# res.net
KiCad netlist of a schematic drawn in EAGLE
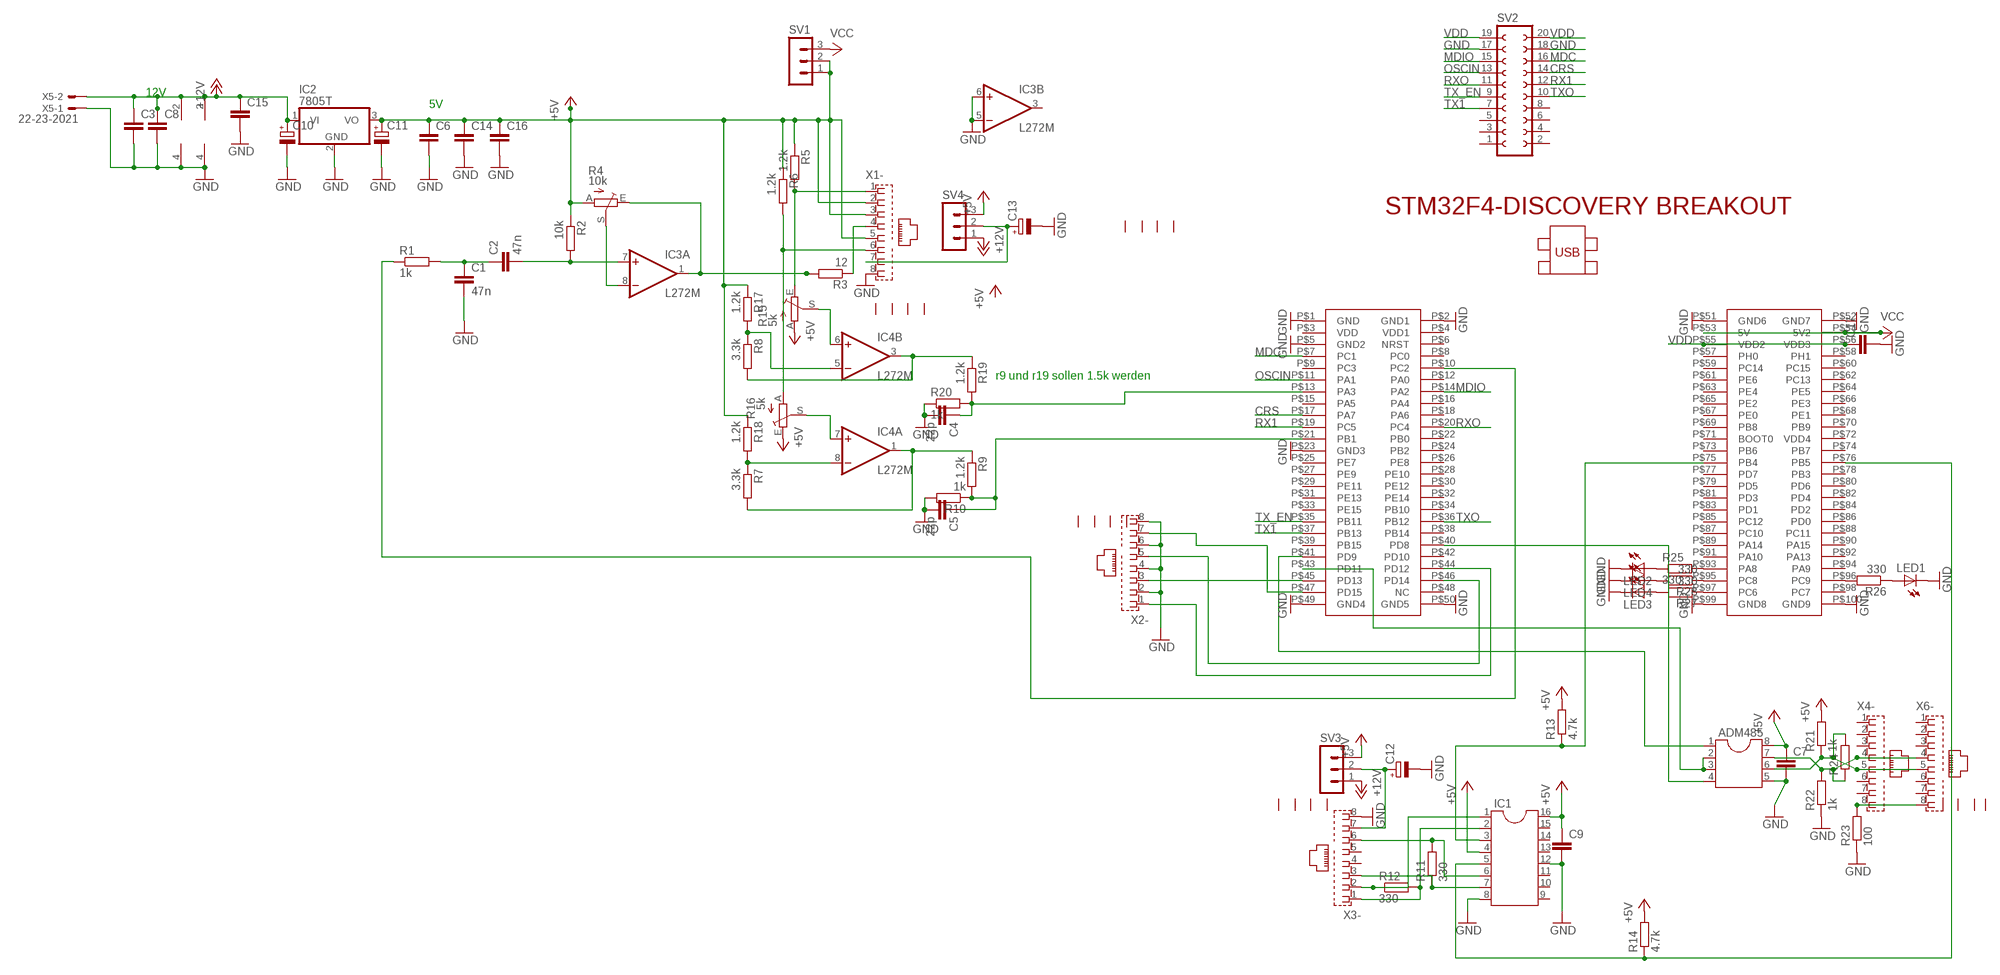
[diagram p0: schematic, sheet 1]

(export (version "E")
  (design (tool "Eeschema 10.0.6"))
  (components
    (comp (ref "ADM485")
      (value "DIL8")
      (footprint "eagle-import:DIL08")
      (libsource (lib "eagle-import") (part "DIL8"))
    )
    (comp (ref "C1")
      (value "47n")
      (footprint "eagle-import:C050-025X075")
      (libsource (lib "eagle-import") (part "C-EU050-025X075"))
    )
    (comp (ref "C2")
      (value "47n")
      (footprint "eagle-import:C050-025X075")
      (libsource (lib "eagle-import") (part "C-EU050-025X075"))
    )
    (comp (ref "C3")
      (value "C-EU050-025X075")
      (footprint "eagle-import:C050-025X075")
      (libsource (lib "eagle-import") (part "C-EU050-025X075"))
    )
    (comp (ref "C4")
      (value "22p")
      (footprint "eagle-import:C050-025X075")
      (libsource (lib "eagle-import") (part "C-EU050-025X075"))
    )
    (comp (ref "C5")
      (value "22p")
      (footprint "eagle-import:C050-025X075")
      (libsource (lib "eagle-import") (part "C-EU050-025X075"))
    )
    (comp (ref "C6")
      (value "C-EU050-025X075")
      (footprint "eagle-import:C050-025X075")
      (libsource (lib "eagle-import") (part "C-EU050-025X075"))
    )
    (comp (ref "C7")
      (value "C-EU050-025X075")
      (footprint "eagle-import:C050-025X075")
      (libsource (lib "eagle-import") (part "C-EU050-025X075"))
    )
    (comp (ref "C8")
      (value "C-EU050-025X075")
      (footprint "eagle-import:C050-025X075")
      (libsource (lib "eagle-import") (part "C-EU050-025X075"))
    )
    (comp (ref "C9")
      (value "C-EU050-025X075")
      (footprint "eagle-import:C050-025X075")
      (libsource (lib "eagle-import") (part "C-EU050-025X075"))
    )
    (comp (ref "C10")
      (value "CPOL-EUE2.5-5")
      (footprint "eagle-import:E2,5-5")
      (libsource (lib "eagle-import") (part "CPOL-EUE2.5-5"))
    )
    (comp (ref "C11")
      (value "CPOL-EUE2.5-5")
      (footprint "eagle-import:E2,5-5")
      (libsource (lib "eagle-import") (part "CPOL-EUE2.5-5"))
    )
    (comp (ref "C12")
      (value "CPOL-EUE2.5-5")
      (footprint "eagle-import:E2,5-5")
      (libsource (lib "eagle-import") (part "CPOL-EUE2.5-5"))
    )
    (comp (ref "C13")
      (value "CPOL-EUE2.5-5")
      (footprint "eagle-import:E2,5-5")
      (libsource (lib "eagle-import") (part "CPOL-EUE2.5-5"))
    )
    (comp (ref "C14")
      (value "C-EU050-025X075")
      (footprint "eagle-import:C050-025X075")
      (libsource (lib "eagle-import") (part "C-EU050-025X075"))
    )
    (comp (ref "C15")
      (value "C-EU050-025X075")
      (footprint "eagle-import:C050-025X075")
      (libsource (lib "eagle-import") (part "C-EU050-025X075"))
    )
    (comp (ref "C16")
      (value "C-EU050-025X075")
      (footprint "eagle-import:C050-025X075")
      (libsource (lib "eagle-import") (part "C-EU050-025X075"))
    )
    (comp (ref "C17")
      (value "C-EU050-025X075")
      (footprint "eagle-import:C050-025X075")
      (libsource (lib "eagle-import") (part "C-EU050-025X075"))
    )
    (comp (ref "IC1")
      (value "DIL16")
      (footprint "eagle-import:DIL16")
      (libsource (lib "eagle-import") (part "DIL16"))
    )
    (comp (ref "IC2")
      (value "7805T")
      (footprint "eagle-import:TO220H")
      (libsource (lib "eagle-import") (part "78T05"))
    )
    (comp (ref "IC3")
      (value "L272M")
      (footprint "eagle-import:DIL08")
      (libsource (lib "eagle-import") (part "L272M"))
    )
    (comp (ref "IC4")
      (value "L272M")
      (footprint "eagle-import:DIL08")
      (libsource (lib "eagle-import") (part "L272M"))
    )
    (comp (ref "LED1")
      (value "LED3MM")
      (footprint "eagle-import:LED3MM")
      (libsource (lib "eagle-import") (part "LED3MM"))
    )
    (comp (ref "LED2")
      (value "LED3MM")
      (footprint "eagle-import:LED3MM")
      (libsource (lib "eagle-import") (part "LED3MM"))
    )
    (comp (ref "LED3")
      (value "LED3MM")
      (footprint "eagle-import:LED3MM")
      (libsource (lib "eagle-import") (part "LED3MM"))
    )
    (comp (ref "LED4")
      (value "LED3MM")
      (footprint "eagle-import:LED3MM")
      (libsource (lib "eagle-import") (part "LED3MM"))
    )
    (comp (ref "R1")
      (value "1k")
      (footprint "eagle-import:0204_7")
      (libsource (lib "eagle-import") (part "R-EU_0204/7"))
    )
    (comp (ref "R2")
      (value "10k")
      (footprint "eagle-import:0204_7")
      (libsource (lib "eagle-import") (part "R-EU_0204/7"))
    )
    (comp (ref "R3")
      (value "12")
      (footprint "eagle-import:0204_7")
      (libsource (lib "eagle-import") (part "R-EU_0204/7"))
    )
    (comp (ref "R4")
      (value "10k")
      (footprint "eagle-import:CA6V")
      (libsource (lib "eagle-import") (part "TRIM_EU-CA6V"))
    )
    (comp (ref "R5")
      (value "1.2k")
      (footprint "eagle-import:0204_7")
      (libsource (lib "eagle-import") (part "R-EU_0204/7"))
    )
    (comp (ref "R6")
      (value "1.2k")
      (footprint "eagle-import:0204_7")
      (libsource (lib "eagle-import") (part "R-EU_0204/7"))
    )
    (comp (ref "R7")
      (value "3.3k")
      (footprint "eagle-import:0204_7")
      (libsource (lib "eagle-import") (part "R-EU_0204/7"))
    )
    (comp (ref "R8")
      (value "3.3k")
      (footprint "eagle-import:0204_7")
      (libsource (lib "eagle-import") (part "R-EU_0204/7"))
    )
    (comp (ref "R9")
      (value "1.2k")
      (footprint "eagle-import:0204_7")
      (libsource (lib "eagle-import") (part "R-EU_0204/7"))
    )
    (comp (ref "R10")
      (value "1k")
      (footprint "eagle-import:0204_7")
      (libsource (lib "eagle-import") (part "R-EU_0204/7"))
    )
    (comp (ref "R11")
      (value "330")
      (footprint "eagle-import:0204_7")
      (libsource (lib "eagle-import") (part "R-EU_0204/7"))
    )
    (comp (ref "R12")
      (value "330")
      (footprint "eagle-import:0204_7")
      (libsource (lib "eagle-import") (part "R-EU_0204/7"))
    )
    (comp (ref "R13")
      (value "4.7k")
      (footprint "eagle-import:0204_7")
      (libsource (lib "eagle-import") (part "R-EU_0204/7"))
    )
    (comp (ref "R14")
      (value "4.7k")
      (footprint "eagle-import:0204_7")
      (libsource (lib "eagle-import") (part "R-EU_0204/7"))
    )
    (comp (ref "R15")
      (value "5k")
      (footprint "eagle-import:CA6V")
      (libsource (lib "eagle-import") (part "TRIM_EU-CA6V"))
    )
    (comp (ref "R16")
      (value "5k")
      (footprint "eagle-import:CA6V")
      (libsource (lib "eagle-import") (part "TRIM_EU-CA6V"))
    )
    (comp (ref "R17")
      (value "1.2k")
      (footprint "eagle-import:0204_7")
      (libsource (lib "eagle-import") (part "R-EU_0204/7"))
    )
    (comp (ref "R18")
      (value "1.2k")
      (footprint "eagle-import:0204_7")
      (libsource (lib "eagle-import") (part "R-EU_0204/7"))
    )
    (comp (ref "R19")
      (value "1.2k")
      (footprint "eagle-import:0204_7")
      (libsource (lib "eagle-import") (part "R-EU_0204/7"))
    )
    (comp (ref "R20")
      (value "1k")
      (footprint "eagle-import:0204_7")
      (libsource (lib "eagle-import") (part "R-EU_0204/7"))
    )
    (comp (ref "R21")
      (value "1k")
      (footprint "eagle-import:0204_7")
      (libsource (lib "eagle-import") (part "R-EU_0204/7"))
    )
    (comp (ref "R22")
      (value "1k")
      (footprint "eagle-import:0204_7")
      (libsource (lib "eagle-import") (part "R-EU_0204/7"))
    )
    (comp (ref "R23")
      (value "100")
      (footprint "eagle-import:0204_7")
      (libsource (lib "eagle-import") (part "R-EU_0204/7"))
    )
    (comp (ref "R24")
      (value "R-EU_0204/7")
      (footprint "eagle-import:0204_7")
      (libsource (lib "eagle-import") (part "R-EU_0204/7"))
    )
    (comp (ref "R25")
      (value "330")
      (footprint "eagle-import:0204_7")
      (libsource (lib "eagle-import") (part "R-EU_0204/7"))
    )
    (comp (ref "R26")
      (value "330")
      (footprint "eagle-import:0204_7")
      (libsource (lib "eagle-import") (part "R-EU_0204/7"))
    )
    (comp (ref "R27")
      (value "330")
      (footprint "eagle-import:0204_7")
      (libsource (lib "eagle-import") (part "R-EU_0204/7"))
    )
    (comp (ref "R28")
      (value "330")
      (footprint "eagle-import:0204_7")
      (libsource (lib "eagle-import") (part "R-EU_0204/7"))
    )
    (comp (ref "SV1")
      (value "MA03-1")
      (footprint "eagle-import:MA03-1")
      (libsource (lib "eagle-import") (part "MA03-1"))
    )
    (comp (ref "SV2")
      (value "FE10-2W")
      (footprint "eagle-import:FE10-2W")
      (libsource (lib "eagle-import") (part "FE10-2W"))
    )
    (comp (ref "SV3")
      (value "MA03-1")
      (footprint "eagle-import:MA03-1")
      (libsource (lib "eagle-import") (part "MA03-1"))
    )
    (comp (ref "SV4")
      (value "MA03-1")
      (footprint "eagle-import:MA03-1")
      (libsource (lib "eagle-import") (part "MA03-1"))
    )
    (comp (ref "U$1")
      (value "STM32F4-DISCOVERY")
      (footprint "eagle-import:STM32F4-DISCOVERY")
      (libsource (lib "eagle-import") (part "STM32F4-DISCOVERY"))
    )
    (comp (ref "X1")
      (value "RJ45")
      (footprint "eagle-import:RJ45")
      (libsource (lib "eagle-import") (part "RJ45"))
    )
    (comp (ref "X2")
      (value "RJ45")
      (footprint "eagle-import:RJ45")
      (libsource (lib "eagle-import") (part "RJ45"))
    )
    (comp (ref "X3")
      (value "RJ45")
      (footprint "eagle-import:RJ45")
      (libsource (lib "eagle-import") (part "RJ45"))
    )
    (comp (ref "X4")
      (value "RJ45")
      (footprint "eagle-import:RJ45")
      (libsource (lib "eagle-import") (part "RJ45"))
    )
    (comp (ref "X5")
      (value "22-23-2021")
      (footprint "eagle-import:22-23-2021")
      (fields (field (name "MF") "MOLEX"))
      (libsource (lib "eagle-import") (part "22-23-2021"))
    )
    (comp (ref "X6")
      (value "RJ45")
      (footprint "eagle-import:RJ45")
      (libsource (lib "eagle-import") (part "RJ45"))
    )
  )
  (nets
    (net (code "1") (name "+5V") (class "Default")
      (node (ref "ADM485") (pin "8") (pinfunction "8_8") (pintype "passive"))
      (node (ref "C11") (pin "+") (pinfunction "+_+") (pintype "passive"))
      (node (ref "C14") (pin "1") (pinfunction "1_1") (pintype "passive"))
      (node (ref "C16") (pin "1") (pinfunction "1_1") (pintype "passive"))
      (node (ref "C6") (pin "1") (pinfunction "1_1") (pintype "passive"))
      (node (ref "C7") (pin "1") (pinfunction "1_1") (pintype "passive"))
      (node (ref "C9") (pin "1") (pinfunction "1_1") (pintype "passive"))
      (node (ref "IC1") (pin "16") (pinfunction "16_16") (pintype "passive"))
      (node (ref "IC1") (pin "4") (pinfunction "4_4") (pintype "passive"))
      (node (ref "IC2") (pin "3") (pinfunction "VO_3") (pintype "passive"))
      (node (ref "R13") (pin "2") (pinfunction "2_2") (pintype "passive"))
      (node (ref "R14") (pin "2") (pinfunction "2_2") (pintype "passive"))
      (node (ref "R15") (pin "A") (pinfunction "A_A") (pintype "passive"))
      (node (ref "R16") (pin "E") (pinfunction "E_E") (pintype "passive"))
      (node (ref "R17") (pin "1") (pinfunction "1_1") (pintype "passive"))
      (node (ref "R18") (pin "1") (pinfunction "1_1") (pintype "passive"))
      (node (ref "R2") (pin "1") (pinfunction "1_1") (pintype "passive"))
      (node (ref "R21") (pin "2") (pinfunction "2_2") (pintype "passive"))
      (node (ref "R4") (pin "A") (pinfunction "A_A") (pintype "passive"))
      (node (ref "R5") (pin "1") (pinfunction "1_1") (pintype "passive"))
      (node (ref "R6") (pin "1") (pinfunction "1_1") (pintype "passive"))
      (node (ref "SV1") (pin "1") (pinfunction "1_1") (pintype "passive"))
      (node (ref "SV1") (pin "2") (pinfunction "2_2") (pintype "passive"))
      (node (ref "SV3") (pin "3") (pinfunction "3_3") (pintype "passive"))
      (node (ref "SV4") (pin "3") (pinfunction "3_3") (pintype "passive"))
      (node (ref "X1") (pin "2") (pinfunction "2_2") (pintype "passive"))
      (node (ref "X1") (pin "3") (pinfunction "3_3") (pintype "passive"))
      (node (ref "X1") (pin "5") (pinfunction "5_5") (pintype "passive"))
    )
    (net (code "2") (name "+12V") (class "Default")
      (node (ref "C10") (pin "+") (pinfunction "+_+") (pintype "passive"))
      (node (ref "C15") (pin "1") (pinfunction "1_1") (pintype "passive"))
      (node (ref "C3") (pin "1") (pinfunction "1_1") (pintype "passive"))
      (node (ref "C8") (pin "1") (pinfunction "1_1") (pintype "passive"))
      (node (ref "IC2") (pin "1") (pinfunction "VI_1") (pintype "input"))
      (node (ref "IC3") (pin "2") (pinfunction "V+_2") (pintype "power_in"))
      (node (ref "IC4") (pin "2") (pinfunction "V+_2") (pintype "power_in"))
      (node (ref "SV3") (pin "1") (pinfunction "1_1") (pintype "passive"))
      (node (ref "SV4") (pin "1") (pinfunction "1_1") (pintype "passive"))
      (node (ref "X5") (pin "2") (pinfunction "S_2") (pintype "passive"))
    )
    (net (code "3") (name "/CRS") (class "Default")
      (node (ref "SV2") (pin "14") (pinfunction "14_14") (pintype "passive"))
      (node (ref "U$1") (pin "P$17") (pinfunction "PA7_P$17") (pintype "bidirectional"))
    )
    (net (code "4") (name "/MDC") (class "Default")
      (node (ref "SV2") (pin "16") (pinfunction "16_16") (pintype "passive"))
      (node (ref "U$1") (pin "P$7") (pinfunction "PC1_P$7") (pintype "bidirectional"))
    )
    (net (code "5") (name "/MDIO") (class "Default")
      (node (ref "SV2") (pin "15") (pinfunction "15_15") (pintype "passive"))
      (node (ref "U$1") (pin "P$14") (pinfunction "PA2_P$14") (pintype "bidirectional"))
    )
    (net (code "6") (name "/OSCIN") (class "Default")
      (node (ref "SV2") (pin "13") (pinfunction "13_13") (pintype "passive"))
      (node (ref "U$1") (pin "P$11") (pinfunction "PA1_P$11") (pintype "bidirectional"))
    )
    (net (code "7") (name "/RX1") (class "Default")
      (node (ref "SV2") (pin "12") (pinfunction "12_12") (pintype "passive"))
      (node (ref "U$1") (pin "P$19") (pinfunction "PC5_P$19") (pintype "bidirectional"))
    )
    (net (code "8") (name "/RXO") (class "Default")
      (node (ref "SV2") (pin "11") (pinfunction "11_11") (pintype "passive"))
      (node (ref "U$1") (pin "P$20") (pinfunction "PC4_P$20") (pintype "bidirectional"))
    )
    (net (code "9") (name "/TX1") (class "Default")
      (node (ref "SV2") (pin "7") (pinfunction "7_7") (pintype "passive"))
      (node (ref "U$1") (pin "P$37") (pinfunction "PB13_P$37") (pintype "bidirectional"))
    )
    (net (code "10") (name "/TXO") (class "Default")
      (node (ref "SV2") (pin "10") (pinfunction "10_10") (pintype "passive"))
      (node (ref "U$1") (pin "P$36") (pinfunction "PB12_P$36") (pintype "bidirectional"))
    )
    (net (code "11") (name "/TX_EN") (class "Default")
      (node (ref "SV2") (pin "9") (pinfunction "9_9") (pintype "passive"))
      (node (ref "U$1") (pin "P$35") (pinfunction "PB11_P$35") (pintype "bidirectional"))
    )
    (net (code "12") (name "/VDD") (class "Default")
      (node (ref "C17") (pin "1") (pinfunction "1_1") (pintype "passive"))
      (node (ref "SV2") (pin "19") (pinfunction "19_19") (pintype "passive"))
      (node (ref "SV2") (pin "20") (pinfunction "20_20") (pintype "passive"))
      (node (ref "U$1") (pin "P$55") (pinfunction "VDD2_P$55") (pintype "bidirectional"))
      (node (ref "U$1") (pin "P$56") (pinfunction "VDD3_P$56") (pintype "bidirectional"))
    )
    (net (code "13") (name "GND") (class "Default")
      (node (ref "ADM485") (pin "5") (pinfunction "5_5") (pintype "passive"))
      (node (ref "C1") (pin "2") (pinfunction "2_2") (pintype "passive"))
      (node (ref "C10") (pin "-") (pinfunction "-_-") (pintype "passive"))
      (node (ref "C11") (pin "-") (pinfunction "-_-") (pintype "passive"))
      (node (ref "C12") (pin "-") (pinfunction "-_-") (pintype "passive"))
      (node (ref "C13") (pin "-") (pinfunction "-_-") (pintype "passive"))
      (node (ref "C14") (pin "2") (pinfunction "2_2") (pintype "passive"))
      (node (ref "C15") (pin "2") (pinfunction "2_2") (pintype "passive"))
      (node (ref "C16") (pin "2") (pinfunction "2_2") (pintype "passive"))
      (node (ref "C17") (pin "2") (pinfunction "2_2") (pintype "passive"))
      (node (ref "C3") (pin "2") (pinfunction "2_2") (pintype "passive"))
      (node (ref "C4") (pin "2") (pinfunction "2_2") (pintype "passive"))
      (node (ref "C5") (pin "2") (pinfunction "2_2") (pintype "passive"))
      (node (ref "C6") (pin "2") (pinfunction "2_2") (pintype "passive"))
      (node (ref "C7") (pin "2") (pinfunction "2_2") (pintype "passive"))
      (node (ref "C8") (pin "2") (pinfunction "2_2") (pintype "passive"))
      (node (ref "C9") (pin "2") (pinfunction "2_2") (pintype "passive"))
      (node (ref "IC1") (pin "12") (pinfunction "12_12") (pintype "passive"))
      (node (ref "IC1") (pin "8") (pinfunction "8_8") (pintype "passive"))
      (node (ref "IC2") (pin "2") (pinfunction "GND_2") (pintype "passive"))
      (node (ref "IC3") (pin "4") (pinfunction "GND_4") (pintype "power_in"))
      (node (ref "IC3") (pin "5") (pinfunction "-IN_5") (pintype "input"))
      (node (ref "IC3") (pin "6") (pinfunction "+IN_6") (pintype "input"))
      (node (ref "IC4") (pin "4") (pinfunction "GND_4") (pintype "power_in"))
      (node (ref "LED1") (pin "K") (pinfunction "C_K") (pintype "passive"))
      (node (ref "LED2") (pin "K") (pinfunction "C_K") (pintype "passive"))
      (node (ref "LED3") (pin "K") (pinfunction "C_K") (pintype "passive"))
      (node (ref "LED4") (pin "K") (pinfunction "C_K") (pintype "passive"))
      (node (ref "R10") (pin "2") (pinfunction "2_2") (pintype "passive"))
      (node (ref "R20") (pin "1") (pinfunction "1_1") (pintype "passive"))
      (node (ref "R22") (pin "1") (pinfunction "1_1") (pintype "passive"))
      (node (ref "R23") (pin "1") (pinfunction "1_1") (pintype "passive"))
      (node (ref "SV2") (pin "17") (pinfunction "17_17") (pintype "passive"))
      (node (ref "SV2") (pin "18") (pinfunction "18_18") (pintype "passive"))
      (node (ref "U$1") (pin "P$1") (pinfunction "GND_P$1") (pintype "bidirectional"))
      (node (ref "U$1") (pin "P$100") (pinfunction "GND9_P$100") (pintype "bidirectional"))
      (node (ref "U$1") (pin "P$2") (pinfunction "GND1_P$2") (pintype "bidirectional"))
      (node (ref "U$1") (pin "P$23") (pinfunction "GND3_P$23") (pintype "bidirectional"))
      (node (ref "U$1") (pin "P$49") (pinfunction "GND4_P$49") (pintype "bidirectional"))
      (node (ref "U$1") (pin "P$5") (pinfunction "GND2_P$5") (pintype "bidirectional"))
      (node (ref "U$1") (pin "P$50") (pinfunction "GND5_P$50") (pintype "bidirectional"))
      (node (ref "U$1") (pin "P$51") (pinfunction "GND6_P$51") (pintype "bidirectional"))
      (node (ref "U$1") (pin "P$52") (pinfunction "GND7_P$52") (pintype "bidirectional"))
      (node (ref "U$1") (pin "P$99") (pinfunction "GND8_P$99") (pintype "bidirectional"))
      (node (ref "X1") (pin "8") (pinfunction "8_8") (pintype "passive"))
      (node (ref "X2") (pin "2") (pinfunction "2_2") (pintype "passive"))
      (node (ref "X2") (pin "4") (pinfunction "4_4") (pintype "passive"))
      (node (ref "X2") (pin "6") (pinfunction "6_6") (pintype "passive"))
      (node (ref "X2") (pin "8") (pinfunction "8_8") (pintype "passive"))
      (node (ref "X3") (pin "8") (pinfunction "8_8") (pintype "passive"))
      (node (ref "X5") (pin "1") (pinfunction "S_1") (pintype "passive"))
    )
    (net (code "14") (name "Net-(ADM485-Pad6)") (class "Default")
      (node (ref "ADM485") (pin "6") (pinfunction "6_6") (pintype "passive"))
      (node (ref "R21") (pin "1") (pinfunction "1_1") (pintype "passive"))
      (node (ref "R24") (pin "2") (pinfunction "2_2") (pintype "passive"))
      (node (ref "X4") (pin "5") (pinfunction "5_5") (pintype "passive"))
      (node (ref "X6") (pin "5") (pinfunction "5_5") (pintype "passive"))
    )
    (net (code "15") (name "Net-(ADM485-Pad7)") (class "Default")
      (node (ref "ADM485") (pin "7") (pinfunction "7_7") (pintype "passive"))
      (node (ref "R22") (pin "2") (pinfunction "2_2") (pintype "passive"))
      (node (ref "R24") (pin "1") (pinfunction "1_1") (pintype "passive"))
      (node (ref "X4") (pin "4") (pinfunction "4_4") (pintype "passive"))
      (node (ref "X6") (pin "4") (pinfunction "4_4") (pintype "passive"))
    )
    (net (code "16") (name "Net-(C1-Pad1)") (class "Default")
      (node (ref "C1") (pin "1") (pinfunction "1_1") (pintype "passive"))
      (node (ref "C2") (pin "1") (pinfunction "1_1") (pintype "passive"))
      (node (ref "R1") (pin "2") (pinfunction "2_2") (pintype "passive"))
    )
    (net (code "17") (name "Net-(C12-Pad+)") (class "Default")
      (node (ref "C12") (pin "+") (pinfunction "+_+") (pintype "passive"))
      (node (ref "SV3") (pin "2") (pinfunction "2_2") (pintype "passive"))
      (node (ref "X3") (pin "7") (pinfunction "7_7") (pintype "passive"))
    )
    (net (code "18") (name "Net-(C13-Pad+)") (class "Default")
      (node (ref "C13") (pin "+") (pinfunction "+_+") (pintype "passive"))
      (node (ref "SV4") (pin "2") (pinfunction "2_2") (pintype "passive"))
      (node (ref "X1") (pin "7") (pinfunction "7_7") (pintype "passive"))
    )
    (net (code "19") (name "Net-(IC1-Pad1)") (class "Default")
      (node (ref "IC1") (pin "1") (pinfunction "1_1") (pintype "passive"))
      (node (ref "R12") (pin "1") (pinfunction "1_1") (pintype "passive"))
      (node (ref "X3") (pin "2") (pinfunction "2_2") (pintype "passive"))
    )
    (net (code "20") (name "Net-(IC1-Pad2)") (class "Default")
      (node (ref "IC1") (pin "2") (pinfunction "2_2") (pintype "passive"))
      (node (ref "R12") (pin "2") (pinfunction "2_2") (pintype "passive"))
      (node (ref "X3") (pin "1") (pinfunction "1_1") (pintype "passive"))
    )
    (net (code "21") (name "Net-(IC1-Pad6)") (class "Default")
      (node (ref "IC1") (pin "6") (pinfunction "6_6") (pintype "passive"))
      (node (ref "R11") (pin "2") (pinfunction "2_2") (pintype "passive"))
      (node (ref "X3") (pin "6") (pinfunction "6_6") (pintype "passive"))
    )
    (net (code "22") (name "Net-(IC1-Pad7)") (class "Default")
      (node (ref "IC1") (pin "7") (pinfunction "7_7") (pintype "passive"))
      (node (ref "R11") (pin "1") (pinfunction "1_1") (pintype "passive"))
      (node (ref "X3") (pin "3") (pinfunction "3_3") (pintype "passive"))
    )
    (net (code "23") (name "Net-(IC3A-+IN)") (class "Default")
      (node (ref "C2") (pin "2") (pinfunction "2_2") (pintype "passive"))
      (node (ref "IC3") (pin "7") (pinfunction "+IN_7") (pintype "input"))
      (node (ref "R2") (pin "2") (pinfunction "2_2") (pintype "passive"))
    )
    (net (code "24") (name "Net-(IC3A--IN)") (class "Default")
      (node (ref "IC3") (pin "8") (pinfunction "-IN_8") (pintype "input"))
      (node (ref "R4") (pin "S") (pinfunction "S_S") (pintype "passive"))
    )
    (net (code "25") (name "Net-(IC3A-OUT)") (class "Default")
      (node (ref "IC3") (pin "1") (pinfunction "OUT_1") (pintype "output"))
      (node (ref "R3") (pin "2") (pinfunction "2_2") (pintype "passive"))
      (node (ref "R4") (pin "E") (pinfunction "E_E") (pintype "passive"))
    )
    (net (code "26") (name "Net-(IC4A-+IN)") (class "Default")
      (node (ref "IC4") (pin "7") (pinfunction "+IN_7") (pintype "input"))
      (node (ref "R16") (pin "S") (pinfunction "S_S") (pintype "passive"))
    )
    (net (code "27") (name "Net-(IC4A--IN)") (class "Default")
      (node (ref "IC4") (pin "8") (pinfunction "-IN_8") (pintype "input"))
      (node (ref "R18") (pin "2") (pinfunction "2_2") (pintype "passive"))
      (node (ref "R7") (pin "1") (pinfunction "1_1") (pintype "passive"))
    )
    (net (code "28") (name "Net-(IC4A-OUT)") (class "Default")
      (node (ref "IC4") (pin "1") (pinfunction "OUT_1") (pintype "output"))
      (node (ref "R7") (pin "2") (pinfunction "2_2") (pintype "passive"))
      (node (ref "R9") (pin "1") (pinfunction "1_1") (pintype "passive"))
    )
    (net (code "29") (name "Net-(IC4B-+IN)") (class "Default")
      (node (ref "IC4") (pin "6") (pinfunction "+IN_6") (pintype "input"))
      (node (ref "R15") (pin "S") (pinfunction "S_S") (pintype "passive"))
    )
    (net (code "30") (name "Net-(IC4B--IN)") (class "Default")
      (node (ref "IC4") (pin "5") (pinfunction "-IN_5") (pintype "input"))
      (node (ref "R17") (pin "2") (pinfunction "2_2") (pintype "passive"))
      (node (ref "R8") (pin "1") (pinfunction "1_1") (pintype "passive"))
    )
    (net (code "31") (name "Net-(IC4B-OUT)") (class "Default")
      (node (ref "IC4") (pin "3") (pinfunction "OUT_3") (pintype "output"))
      (node (ref "R19") (pin "1") (pinfunction "1_1") (pintype "passive"))
      (node (ref "R8") (pin "2") (pinfunction "2_2") (pintype "passive"))
    )
    (net (code "32") (name "Net-(LED1-PadA)") (class "Default")
      (node (ref "LED1") (pin "A") (pinfunction "A_A") (pintype "passive"))
      (node (ref "R26") (pin "1") (pinfunction "1_1") (pintype "passive"))
    )
    (net (code "33") (name "Net-(LED2-PadA)") (class "Default")
      (node (ref "LED2") (pin "A") (pinfunction "A_A") (pintype "passive"))
      (node (ref "R25") (pin "1") (pinfunction "1_1") (pintype "passive"))
    )
    (net (code "34") (name "Net-(LED3-PadA)") (class "Default")
      (node (ref "LED3") (pin "A") (pinfunction "A_A") (pintype "passive"))
      (node (ref "R27") (pin "2") (pinfunction "2_2") (pintype "passive"))
    )
    (net (code "35") (name "Net-(LED4-PadA)") (class "Default")
      (node (ref "LED4") (pin "A") (pinfunction "A_A") (pintype "passive"))
      (node (ref "R28") (pin "2") (pinfunction "2_2") (pintype "passive"))
    )
    (net (code "36") (name "Net-(R3-Pad1)") (class "Default")
      (node (ref "R3") (pin "1") (pinfunction "1_1") (pintype "passive"))
      (node (ref "X1") (pin "4") (pinfunction "4_4") (pintype "passive"))
    )
    (net (code "37") (name "Net-(R15-PadE)") (class "Default")
      (node (ref "R15") (pin "E") (pinfunction "E_E") (pintype "passive"))
      (node (ref "R5") (pin "2") (pinfunction "2_2") (pintype "passive"))
      (node (ref "X1") (pin "1") (pinfunction "1_1") (pintype "passive"))
    )
    (net (code "38") (name "Net-(R16-PadA)") (class "Default")
      (node (ref "R16") (pin "A") (pinfunction "A_A") (pintype "passive"))
      (node (ref "R6") (pin "2") (pinfunction "2_2") (pintype "passive"))
      (node (ref "X1") (pin "6") (pinfunction "6_6") (pintype "passive"))
    )
    (net (code "39") (name "Net-(R23-Pad2)") (class "Default")
      (node (ref "R23") (pin "2") (pinfunction "2_2") (pintype "passive"))
      (node (ref "X4") (pin "8") (pinfunction "8_8") (pintype "passive"))
      (node (ref "X6") (pin "8") (pinfunction "8_8") (pintype "passive"))
    )
    (net (code "40") (name "Net-(U$1-PA3)") (class "Default")
      (node (ref "C4") (pin "1") (pinfunction "1_1") (pintype "passive"))
      (node (ref "R19") (pin "2") (pinfunction "2_2") (pintype "passive"))
      (node (ref "R20") (pin "2") (pinfunction "2_2") (pintype "passive"))
      (node (ref "U$1") (pin "P$13") (pinfunction "PA3_P$13") (pintype "bidirectional"))
    )
    (net (code "41") (name "Net-(U$1-PA8)") (class "Default")
      (node (ref "R25") (pin "2") (pinfunction "2_2") (pintype "passive"))
      (node (ref "U$1") (pin "P$93") (pinfunction "PA8_P$93") (pintype "bidirectional"))
    )
    (net (code "42") (name "Net-(U$1-PB1)") (class "Default")
      (node (ref "C5") (pin "1") (pinfunction "1_1") (pintype "passive"))
      (node (ref "R10") (pin "1") (pinfunction "1_1") (pintype "passive"))
      (node (ref "R9") (pin "2") (pinfunction "2_2") (pintype "passive"))
      (node (ref "U$1") (pin "P$21") (pinfunction "PB1_P$21") (pintype "bidirectional"))
    )
    (net (code "43") (name "Net-(U$1-PB4)") (class "Default")
      (node (ref "IC1") (pin "3") (pinfunction "3_3") (pintype "passive"))
      (node (ref "R13") (pin "1") (pinfunction "1_1") (pintype "passive"))
      (node (ref "U$1") (pin "P$75") (pinfunction "PB4_P$75") (pintype "bidirectional"))
    )
    (net (code "44") (name "Net-(U$1-PB5)") (class "Default")
      (node (ref "IC1") (pin "5") (pinfunction "5_5") (pintype "passive"))
      (node (ref "R14") (pin "1") (pinfunction "1_1") (pintype "passive"))
      (node (ref "U$1") (pin "P$76") (pinfunction "PB5_P$76") (pintype "bidirectional"))
    )
    (net (code "45") (name "Net-(U$1-PC2)") (class "Default")
      (node (ref "R1") (pin "1") (pinfunction "1_1") (pintype "passive"))
      (node (ref "U$1") (pin "P$10") (pinfunction "PC2_P$10") (pintype "bidirectional"))
    )
    (net (code "46") (name "Net-(U$1-PC6)") (class "Default")
      (node (ref "R27") (pin "1") (pinfunction "1_1") (pintype "passive"))
      (node (ref "U$1") (pin "P$97") (pinfunction "PC6_P$97") (pintype "bidirectional"))
    )
    (net (code "47") (name "Net-(U$1-PC8)") (class "Default")
      (node (ref "R28") (pin "1") (pinfunction "1_1") (pintype "passive"))
      (node (ref "U$1") (pin "P$95") (pinfunction "PC8_P$95") (pintype "bidirectional"))
    )
    (net (code "48") (name "Net-(U$1-PC9)") (class "Default")
      (node (ref "R26") (pin "2") (pinfunction "2_2") (pintype "passive"))
      (node (ref "U$1") (pin "P$96") (pinfunction "PC9_P$96") (pintype "bidirectional"))
    )
    (net (code "49") (name "Net-(U$1-PD8)") (class "Default")
      (node (ref "ADM485") (pin "4") (pinfunction "4_4") (pintype "passive"))
      (node (ref "U$1") (pin "P$40") (pinfunction "PD8_P$40") (pintype "bidirectional"))
    )
    (net (code "50") (name "Net-(U$1-PD9)") (class "Default")
      (node (ref "ADM485") (pin "1") (pinfunction "1_1") (pintype "passive"))
      (node (ref "U$1") (pin "P$41") (pinfunction "PD9_P$41") (pintype "bidirectional"))
    )
    (net (code "51") (name "Net-(U$1-PD11)") (class "Default")
      (node (ref "ADM485") (pin "2") (pinfunction "2_2") (pintype "passive"))
      (node (ref "ADM485") (pin "3") (pinfunction "3_3") (pintype "passive"))
      (node (ref "U$1") (pin "P$43") (pinfunction "PD11_P$43") (pintype "bidirectional"))
    )
    (net (code "52") (name "Net-(U$1-PD12)") (class "Default")
      (node (ref "U$1") (pin "P$44") (pinfunction "PD12_P$44") (pintype "bidirectional"))
      (node (ref "X2") (pin "1") (pinfunction "1_1") (pintype "passive"))
    )
    (net (code "53") (name "Net-(U$1-PD13)") (class "Default")
      (node (ref "U$1") (pin "P$45") (pinfunction "PD13_P$45") (pintype "bidirectional"))
      (node (ref "X2") (pin "3") (pinfunction "3_3") (pintype "passive"))
    )
    (net (code "54") (name "Net-(U$1-PD14)") (class "Default")
      (node (ref "U$1") (pin "P$46") (pinfunction "PD14_P$46") (pintype "bidirectional"))
      (node (ref "X2") (pin "5") (pinfunction "5_5") (pintype "passive"))
    )
    (net (code "55") (name "Net-(U$1-PD15)") (class "Default")
      (node (ref "U$1") (pin "P$47") (pinfunction "PD15_P$47") (pintype "bidirectional"))
      (node (ref "X2") (pin "7") (pinfunction "7_7") (pintype "passive"))
    )
    (net (code "56") (name "VCC") (class "Default")
      (node (ref "SV1") (pin "3") (pinfunction "3_3") (pintype "passive"))
      (node (ref "U$1") (pin "P$53") (pinfunction "5V_P$53") (pintype "bidirectional"))
      (node (ref "U$1") (pin "P$54") (pinfunction "5V2_P$54") (pintype "bidirectional"))
    )
    (net (code "57") (name "unconnected-(IC1-Pad9)") (class "Default")
      (node (ref "IC1") (pin "9") (pinfunction "9_9") (pintype "passive"))
    )
    (net (code "58") (name "unconnected-(IC1-Pad10)") (class "Default")
      (node (ref "IC1") (pin "10") (pinfunction "10_10") (pintype "passive"))
    )
    (net (code "59") (name "unconnected-(IC1-Pad11)") (class "Default")
      (node (ref "IC1") (pin "11") (pinfunction "11_11") (pintype "passive"))
    )
    (net (code "60") (name "unconnected-(IC1-Pad13)") (class "Default")
      (node (ref "IC1") (pin "13") (pinfunction "13_13") (pintype "passive"))
    )
    (net (code "61") (name "unconnected-(IC1-Pad14)") (class "Default")
      (node (ref "IC1") (pin "14") (pinfunction "14_14") (pintype "passive"))
    )
    (net (code "62") (name "unconnected-(IC1-Pad15)") (class "Default")
      (node (ref "IC1") (pin "15") (pinfunction "15_15") (pintype "passive"))
    )
    (net (code "63") (name "unconnected-(IC3B-OUT-Pad3)") (class "Default")
      (node (ref "IC3") (pin "3") (pinfunction "OUT_3") (pintype "output"))
    )
    (net (code "64") (name "unconnected-(SV2-Pad1)") (class "Default")
      (node (ref "SV2") (pin "1") (pinfunction "1_1") (pintype "passive"))
    )
    (net (code "65") (name "unconnected-(SV2-Pad2)") (class "Default")
      (node (ref "SV2") (pin "2") (pinfunction "2_2") (pintype "passive"))
    )
    (net (code "66") (name "unconnected-(SV2-Pad3)") (class "Default")
      (node (ref "SV2") (pin "3") (pinfunction "3_3") (pintype "passive"))
    )
    (net (code "67") (name "unconnected-(SV2-Pad4)") (class "Default")
      (node (ref "SV2") (pin "4") (pinfunction "4_4") (pintype "passive"))
    )
    (net (code "68") (name "unconnected-(SV2-Pad5)") (class "Default")
      (node (ref "SV2") (pin "5") (pinfunction "5_5") (pintype "passive"))
    )
    (net (code "69") (name "unconnected-(SV2-Pad6)") (class "Default")
      (node (ref "SV2") (pin "6") (pinfunction "6_6") (pintype "passive"))
    )
    (net (code "70") (name "unconnected-(SV2-Pad8)") (class "Default")
      (node (ref "SV2") (pin "8") (pinfunction "8_8") (pintype "passive"))
    )
    (net (code "71") (name "unconnected-(U$1-BOOT0-PadP$71)") (class "Default")
      (node (ref "U$1") (pin "P$71") (pinfunction "BOOT0_P$71") (pintype "bidirectional"))
    )
    (net (code "72") (name "unconnected-(U$1-NC-PadP$48)") (class "Default")
      (node (ref "U$1") (pin "P$48") (pinfunction "NC_P$48") (pintype "bidirectional"))
    )
    (net (code "73") (name "unconnected-(U$1-NRST-PadP$6)") (class "Default")
      (node (ref "U$1") (pin "P$6") (pinfunction "NRST_P$6") (pintype "bidirectional"))
    )
    (net (code "74") (name "unconnected-(U$1-PA0-PadP$12)") (class "Default")
      (node (ref "U$1") (pin "P$12") (pinfunction "PA0_P$12") (pintype "bidirectional"))
    )
    (net (code "75") (name "unconnected-(U$1-PA4-PadP$16)") (class "Default")
      (node (ref "U$1") (pin "P$16") (pinfunction "PA4_P$16") (pintype "bidirectional"))
    )
    (net (code "76") (name "unconnected-(U$1-PA5-PadP$15)") (class "Default")
      (node (ref "U$1") (pin "P$15") (pinfunction "PA5_P$15") (pintype "bidirectional"))
    )
    (net (code "77") (name "unconnected-(U$1-PA6-PadP$18)") (class "Default")
      (node (ref "U$1") (pin "P$18") (pinfunction "PA6_P$18") (pintype "bidirectional"))
    )
    (net (code "78") (name "unconnected-(U$1-PA9-PadP$94)") (class "Default")
      (node (ref "U$1") (pin "P$94") (pinfunction "PA9_P$94") (pintype "bidirectional"))
    )
    (net (code "79") (name "unconnected-(U$1-PA10-PadP$91)") (class "Default")
      (node (ref "U$1") (pin "P$91") (pinfunction "PA10_P$91") (pintype "bidirectional"))
    )
    (net (code "80") (name "unconnected-(U$1-PA13-PadP$92)") (class "Default")
      (node (ref "U$1") (pin "P$92") (pinfunction "PA13_P$92") (pintype "bidirectional"))
    )
    (net (code "81") (name "unconnected-(U$1-PA14-PadP$89)") (class "Default")
      (node (ref "U$1") (pin "P$89") (pinfunction "PA14_P$89") (pintype "bidirectional"))
    )
    (net (code "82") (name "unconnected-(U$1-PA15-PadP$90)") (class "Default")
      (node (ref "U$1") (pin "P$90") (pinfunction "PA15_P$90") (pintype "bidirectional"))
    )
    (net (code "83") (name "unconnected-(U$1-PB0-PadP$22)") (class "Default")
      (node (ref "U$1") (pin "P$22") (pinfunction "PB0_P$22") (pintype "bidirectional"))
    )
    (net (code "84") (name "unconnected-(U$1-PB2-PadP$24)") (class "Default")
      (node (ref "U$1") (pin "P$24") (pinfunction "PB2_P$24") (pintype "bidirectional"))
    )
    (net (code "85") (name "unconnected-(U$1-PB3-PadP$78)") (class "Default")
      (node (ref "U$1") (pin "P$78") (pinfunction "PB3_P$78") (pintype "bidirectional"))
    )
    (net (code "86") (name "unconnected-(U$1-PB6-PadP$73)") (class "Default")
      (node (ref "U$1") (pin "P$73") (pinfunction "PB6_P$73") (pintype "bidirectional"))
    )
    (net (code "87") (name "unconnected-(U$1-PB7-PadP$74)") (class "Default")
      (node (ref "U$1") (pin "P$74") (pinfunction "PB7_P$74") (pintype "bidirectional"))
    )
    (net (code "88") (name "unconnected-(U$1-PB8-PadP$69)") (class "Default")
      (node (ref "U$1") (pin "P$69") (pinfunction "PB8_P$69") (pintype "bidirectional"))
    )
    (net (code "89") (name "unconnected-(U$1-PB9-PadP$70)") (class "Default")
      (node (ref "U$1") (pin "P$70") (pinfunction "PB9_P$70") (pintype "bidirectional"))
    )
    (net (code "90") (name "unconnected-(U$1-PB10-PadP$34)") (class "Default")
      (node (ref "U$1") (pin "P$34") (pinfunction "PB10_P$34") (pintype "bidirectional"))
    )
    (net (code "91") (name "unconnected-(U$1-PB14-PadP$38)") (class "Default")
      (node (ref "U$1") (pin "P$38") (pinfunction "PB14_P$38") (pintype "bidirectional"))
    )
    (net (code "92") (name "unconnected-(U$1-PB15-PadP$39)") (class "Default")
      (node (ref "U$1") (pin "P$39") (pinfunction "PB15_P$39") (pintype "bidirectional"))
    )
    (net (code "93") (name "unconnected-(U$1-PC0-PadP$8)") (class "Default")
      (node (ref "U$1") (pin "P$8") (pinfunction "PC0_P$8") (pintype "bidirectional"))
    )
    (net (code "94") (name "unconnected-(U$1-PC3-PadP$9)") (class "Default")
      (node (ref "U$1") (pin "P$9") (pinfunction "PC3_P$9") (pintype "bidirectional"))
    )
    (net (code "95") (name "unconnected-(U$1-PC7-PadP$98)") (class "Default")
      (node (ref "U$1") (pin "P$98") (pinfunction "PC7_P$98") (pintype "bidirectional"))
    )
    (net (code "96") (name "unconnected-(U$1-PC10-PadP$87)") (class "Default")
      (node (ref "U$1") (pin "P$87") (pinfunction "PC10_P$87") (pintype "bidirectional"))
    )
    (net (code "97") (name "unconnected-(U$1-PC11-PadP$88)") (class "Default")
      (node (ref "U$1") (pin "P$88") (pinfunction "PC11_P$88") (pintype "bidirectional"))
    )
    (net (code "98") (name "unconnected-(U$1-PC12-PadP$85)") (class "Default")
      (node (ref "U$1") (pin "P$85") (pinfunction "PC12_P$85") (pintype "bidirectional"))
    )
    (net (code "99") (name "unconnected-(U$1-PC13-PadP$62)") (class "Default")
      (node (ref "U$1") (pin "P$62") (pinfunction "PC13_P$62") (pintype "bidirectional"))
    )
    (net (code "100") (name "unconnected-(U$1-PC14-PadP$59)") (class "Default")
      (node (ref "U$1") (pin "P$59") (pinfunction "PC14_P$59") (pintype "bidirectional"))
    )
    (net (code "101") (name "unconnected-(U$1-PC15-PadP$60)") (class "Default")
      (node (ref "U$1") (pin "P$60") (pinfunction "PC15_P$60") (pintype "bidirectional"))
    )
    (net (code "102") (name "unconnected-(U$1-PD0-PadP$86)") (class "Default")
      (node (ref "U$1") (pin "P$86") (pinfunction "PD0_P$86") (pintype "bidirectional"))
    )
    (net (code "103") (name "unconnected-(U$1-PD1-PadP$83)") (class "Default")
      (node (ref "U$1") (pin "P$83") (pinfunction "PD1_P$83") (pintype "bidirectional"))
    )
    (net (code "104") (name "unconnected-(U$1-PD2-PadP$84)") (class "Default")
      (node (ref "U$1") (pin "P$84") (pinfunction "PD2_P$84") (pintype "bidirectional"))
    )
    (net (code "105") (name "unconnected-(U$1-PD3-PadP$81)") (class "Default")
      (node (ref "U$1") (pin "P$81") (pinfunction "PD3_P$81") (pintype "bidirectional"))
    )
    (net (code "106") (name "unconnected-(U$1-PD4-PadP$82)") (class "Default")
      (node (ref "U$1") (pin "P$82") (pinfunction "PD4_P$82") (pintype "bidirectional"))
    )
    (net (code "107") (name "unconnected-(U$1-PD5-PadP$79)") (class "Default")
      (node (ref "U$1") (pin "P$79") (pinfunction "PD5_P$79") (pintype "bidirectional"))
    )
    (net (code "108") (name "unconnected-(U$1-PD6-PadP$80)") (class "Default")
      (node (ref "U$1") (pin "P$80") (pinfunction "PD6_P$80") (pintype "bidirectional"))
    )
    (net (code "109") (name "unconnected-(U$1-PD7-PadP$77)") (class "Default")
      (node (ref "U$1") (pin "P$77") (pinfunction "PD7_P$77") (pintype "bidirectional"))
    )
    (net (code "110") (name "unconnected-(U$1-PD10-PadP$42)") (class "Default")
      (node (ref "U$1") (pin "P$42") (pinfunction "PD10_P$42") (pintype "bidirectional"))
    )
    (net (code "111") (name "unconnected-(U$1-PE0-PadP$67)") (class "Default")
      (node (ref "U$1") (pin "P$67") (pinfunction "PE0_P$67") (pintype "bidirectional"))
    )
    (net (code "112") (name "unconnected-(U$1-PE1-PadP$68)") (class "Default")
      (node (ref "U$1") (pin "P$68") (pinfunction "PE1_P$68") (pintype "bidirectional"))
    )
    (net (code "113") (name "unconnected-(U$1-PE2-PadP$65)") (class "Default")
      (node (ref "U$1") (pin "P$65") (pinfunction "PE2_P$65") (pintype "bidirectional"))
    )
    (net (code "114") (name "unconnected-(U$1-PE3-PadP$66)") (class "Default")
      (node (ref "U$1") (pin "P$66") (pinfunction "PE3_P$66") (pintype "bidirectional"))
    )
    (net (code "115") (name "unconnected-(U$1-PE4-PadP$63)") (class "Default")
      (node (ref "U$1") (pin "P$63") (pinfunction "PE4_P$63") (pintype "bidirectional"))
    )
    (net (code "116") (name "unconnected-(U$1-PE5-PadP$64)") (class "Default")
      (node (ref "U$1") (pin "P$64") (pinfunction "PE5_P$64") (pintype "bidirectional"))
    )
    (net (code "117") (name "unconnected-(U$1-PE6-PadP$61)") (class "Default")
      (node (ref "U$1") (pin "P$61") (pinfunction "PE6_P$61") (pintype "bidirectional"))
    )
    (net (code "118") (name "unconnected-(U$1-PE7-PadP$25)") (class "Default")
      (node (ref "U$1") (pin "P$25") (pinfunction "PE7_P$25") (pintype "bidirectional"))
    )
    (net (code "119") (name "unconnected-(U$1-PE8-PadP$26)") (class "Default")
      (node (ref "U$1") (pin "P$26") (pinfunction "PE8_P$26") (pintype "bidirectional"))
    )
    (net (code "120") (name "unconnected-(U$1-PE9-PadP$27)") (class "Default")
      (node (ref "U$1") (pin "P$27") (pinfunction "PE9_P$27") (pintype "bidirectional"))
    )
    (net (code "121") (name "unconnected-(U$1-PE10-PadP$28)") (class "Default")
      (node (ref "U$1") (pin "P$28") (pinfunction "PE10_P$28") (pintype "bidirectional"))
    )
    (net (code "122") (name "unconnected-(U$1-PE11-PadP$29)") (class "Default")
      (node (ref "U$1") (pin "P$29") (pinfunction "PE11_P$29") (pintype "bidirectional"))
    )
    (net (code "123") (name "unconnected-(U$1-PE12-PadP$30)") (class "Default")
      (node (ref "U$1") (pin "P$30") (pinfunction "PE12_P$30") (pintype "bidirectional"))
    )
    (net (code "124") (name "unconnected-(U$1-PE13-PadP$31)") (class "Default")
      (node (ref "U$1") (pin "P$31") (pinfunction "PE13_P$31") (pintype "bidirectional"))
    )
    (net (code "125") (name "unconnected-(U$1-PE14-PadP$32)") (class "Default")
      (node (ref "U$1") (pin "P$32") (pinfunction "PE14_P$32") (pintype "bidirectional"))
    )
    (net (code "126") (name "unconnected-(U$1-PE15-PadP$33)") (class "Default")
      (node (ref "U$1") (pin "P$33") (pinfunction "PE15_P$33") (pintype "bidirectional"))
    )
    (net (code "127") (name "unconnected-(U$1-PH0-PadP$57)") (class "Default")
      (node (ref "U$1") (pin "P$57") (pinfunction "PH0_P$57") (pintype "bidirectional"))
    )
    (net (code "128") (name "unconnected-(U$1-PH1-PadP$58)") (class "Default")
      (node (ref "U$1") (pin "P$58") (pinfunction "PH1_P$58") (pintype "bidirectional"))
    )
    (net (code "129") (name "unconnected-(U$1-VDD-PadP$3)") (class "Default")
      (node (ref "U$1") (pin "P$3") (pinfunction "VDD_P$3") (pintype "bidirectional"))
    )
    (net (code "130") (name "unconnected-(U$1-VDD1-PadP$4)") (class "Default")
      (node (ref "U$1") (pin "P$4") (pinfunction "VDD1_P$4") (pintype "bidirectional"))
    )
    (net (code "131") (name "unconnected-(U$1-VDD4-PadP$72)") (class "Default")
      (node (ref "U$1") (pin "P$72") (pinfunction "VDD4_P$72") (pintype "bidirectional"))
    )
    (net (code "132") (name "unconnected-(X1B-1-PadG1)") (class "Default")
      (node (ref "X1") (pin "G1") (pinfunction "1_G1") (pintype "passive"))
    )
    (net (code "133") (name "unconnected-(X1C-1-PadG2)") (class "Default")
      (node (ref "X1") (pin "G2") (pinfunction "1_G2") (pintype "passive"))
    )
    (net (code "134") (name "unconnected-(X1D-1-PadG3)") (class "Default")
      (node (ref "X1") (pin "G3") (pinfunction "1_G3") (pintype "passive"))
    )
    (net (code "135") (name "unconnected-(X1E-1-PadG4)") (class "Default")
      (node (ref "X1") (pin "G4") (pinfunction "1_G4") (pintype "passive"))
    )
    (net (code "136") (name "unconnected-(X2B-1-PadG1)") (class "Default")
      (node (ref "X2") (pin "G1") (pinfunction "1_G1") (pintype "passive"))
    )
    (net (code "137") (name "unconnected-(X2C-1-PadG2)") (class "Default")
      (node (ref "X2") (pin "G2") (pinfunction "1_G2") (pintype "passive"))
    )
    (net (code "138") (name "unconnected-(X2D-1-PadG3)") (class "Default")
      (node (ref "X2") (pin "G3") (pinfunction "1_G3") (pintype "passive"))
    )
    (net (code "139") (name "unconnected-(X2E-1-PadG4)") (class "Default")
      (node (ref "X2") (pin "G4") (pinfunction "1_G4") (pintype "passive"))
    )
    (net (code "140") (name "unconnected-(X3-Pad4)") (class "Default")
      (node (ref "X3") (pin "4") (pinfunction "4_4") (pintype "passive"))
    )
    (net (code "141") (name "unconnected-(X3-Pad5)") (class "Default")
      (node (ref "X3") (pin "5") (pinfunction "5_5") (pintype "passive"))
    )
    (net (code "142") (name "unconnected-(X3B-1-PadG1)") (class "Default")
      (node (ref "X3") (pin "G1") (pinfunction "1_G1") (pintype "passive"))
    )
    (net (code "143") (name "unconnected-(X3C-1-PadG2)") (class "Default")
      (node (ref "X3") (pin "G2") (pinfunction "1_G2") (pintype "passive"))
    )
    (net (code "144") (name "unconnected-(X3D-1-PadG3)") (class "Default")
      (node (ref "X3") (pin "G3") (pinfunction "1_G3") (pintype "passive"))
    )
    (net (code "145") (name "unconnected-(X3E-1-PadG4)") (class "Default")
      (node (ref "X3") (pin "G4") (pinfunction "1_G4") (pintype "passive"))
    )
    (net (code "146") (name "unconnected-(X4-Pad1)") (class "Default")
      (node (ref "X4") (pin "1") (pinfunction "1_1") (pintype "passive"))
    )
    (net (code "147") (name "unconnected-(X4-Pad2)") (class "Default")
      (node (ref "X4") (pin "2") (pinfunction "2_2") (pintype "passive"))
    )
    (net (code "148") (name "unconnected-(X4-Pad3)") (class "Default")
      (node (ref "X4") (pin "3") (pinfunction "3_3") (pintype "passive"))
    )
    (net (code "149") (name "unconnected-(X4-Pad6)") (class "Default")
      (node (ref "X4") (pin "6") (pinfunction "6_6") (pintype "passive"))
    )
    (net (code "150") (name "unconnected-(X4-Pad7)") (class "Default")
      (node (ref "X4") (pin "7") (pinfunction "7_7") (pintype "passive"))
    )
    (net (code "151") (name "unconnected-(X4B-1-PadG1)") (class "Default")
      (node (ref "X4") (pin "G1") (pinfunction "1_G1") (pintype "passive"))
    )
    (net (code "152") (name "unconnected-(X4C-1-PadG2)") (class "Default")
      (node (ref "X4") (pin "G2") (pinfunction "1_G2") (pintype "passive"))
    )
    (net (code "153") (name "unconnected-(X4D-1-PadG3)") (class "Default")
      (node (ref "X4") (pin "G3") (pinfunction "1_G3") (pintype "passive"))
    )
    (net (code "154") (name "unconnected-(X4E-1-PadG4)") (class "Default")
      (node (ref "X4") (pin "G4") (pinfunction "1_G4") (pintype "passive"))
    )
    (net (code "155") (name "unconnected-(X6-Pad1)") (class "Default")
      (node (ref "X6") (pin "1") (pinfunction "1_1") (pintype "passive"))
    )
    (net (code "156") (name "unconnected-(X6-Pad2)") (class "Default")
      (node (ref "X6") (pin "2") (pinfunction "2_2") (pintype "passive"))
    )
    (net (code "157") (name "unconnected-(X6-Pad3)") (class "Default")
      (node (ref "X6") (pin "3") (pinfunction "3_3") (pintype "passive"))
    )
    (net (code "158") (name "unconnected-(X6-Pad6)") (class "Default")
      (node (ref "X6") (pin "6") (pinfunction "6_6") (pintype "passive"))
    )
    (net (code "159") (name "unconnected-(X6-Pad7)") (class "Default")
      (node (ref "X6") (pin "7") (pinfunction "7_7") (pintype "passive"))
    )
    (net (code "160") (name "unconnected-(X6B-1-PadG1)") (class "Default")
      (node (ref "X6") (pin "G1") (pinfunction "1_G1") (pintype "passive"))
    )
    (net (code "161") (name "unconnected-(X6C-1-PadG2)") (class "Default")
      (node (ref "X6") (pin "G2") (pinfunction "1_G2") (pintype "passive"))
    )
    (net (code "162") (name "unconnected-(X6D-1-PadG3)") (class "Default")
      (node (ref "X6") (pin "G3") (pinfunction "1_G3") (pintype "passive"))
    )
    (net (code "163") (name "unconnected-(X6E-1-PadG4)") (class "Default")
      (node (ref "X6") (pin "G4") (pinfunction "1_G4") (pintype "passive"))
    )
  )
)
